# tiny-psu-exp-v1_1.net
KiCad netlist of a schematic drawn in EAGLE
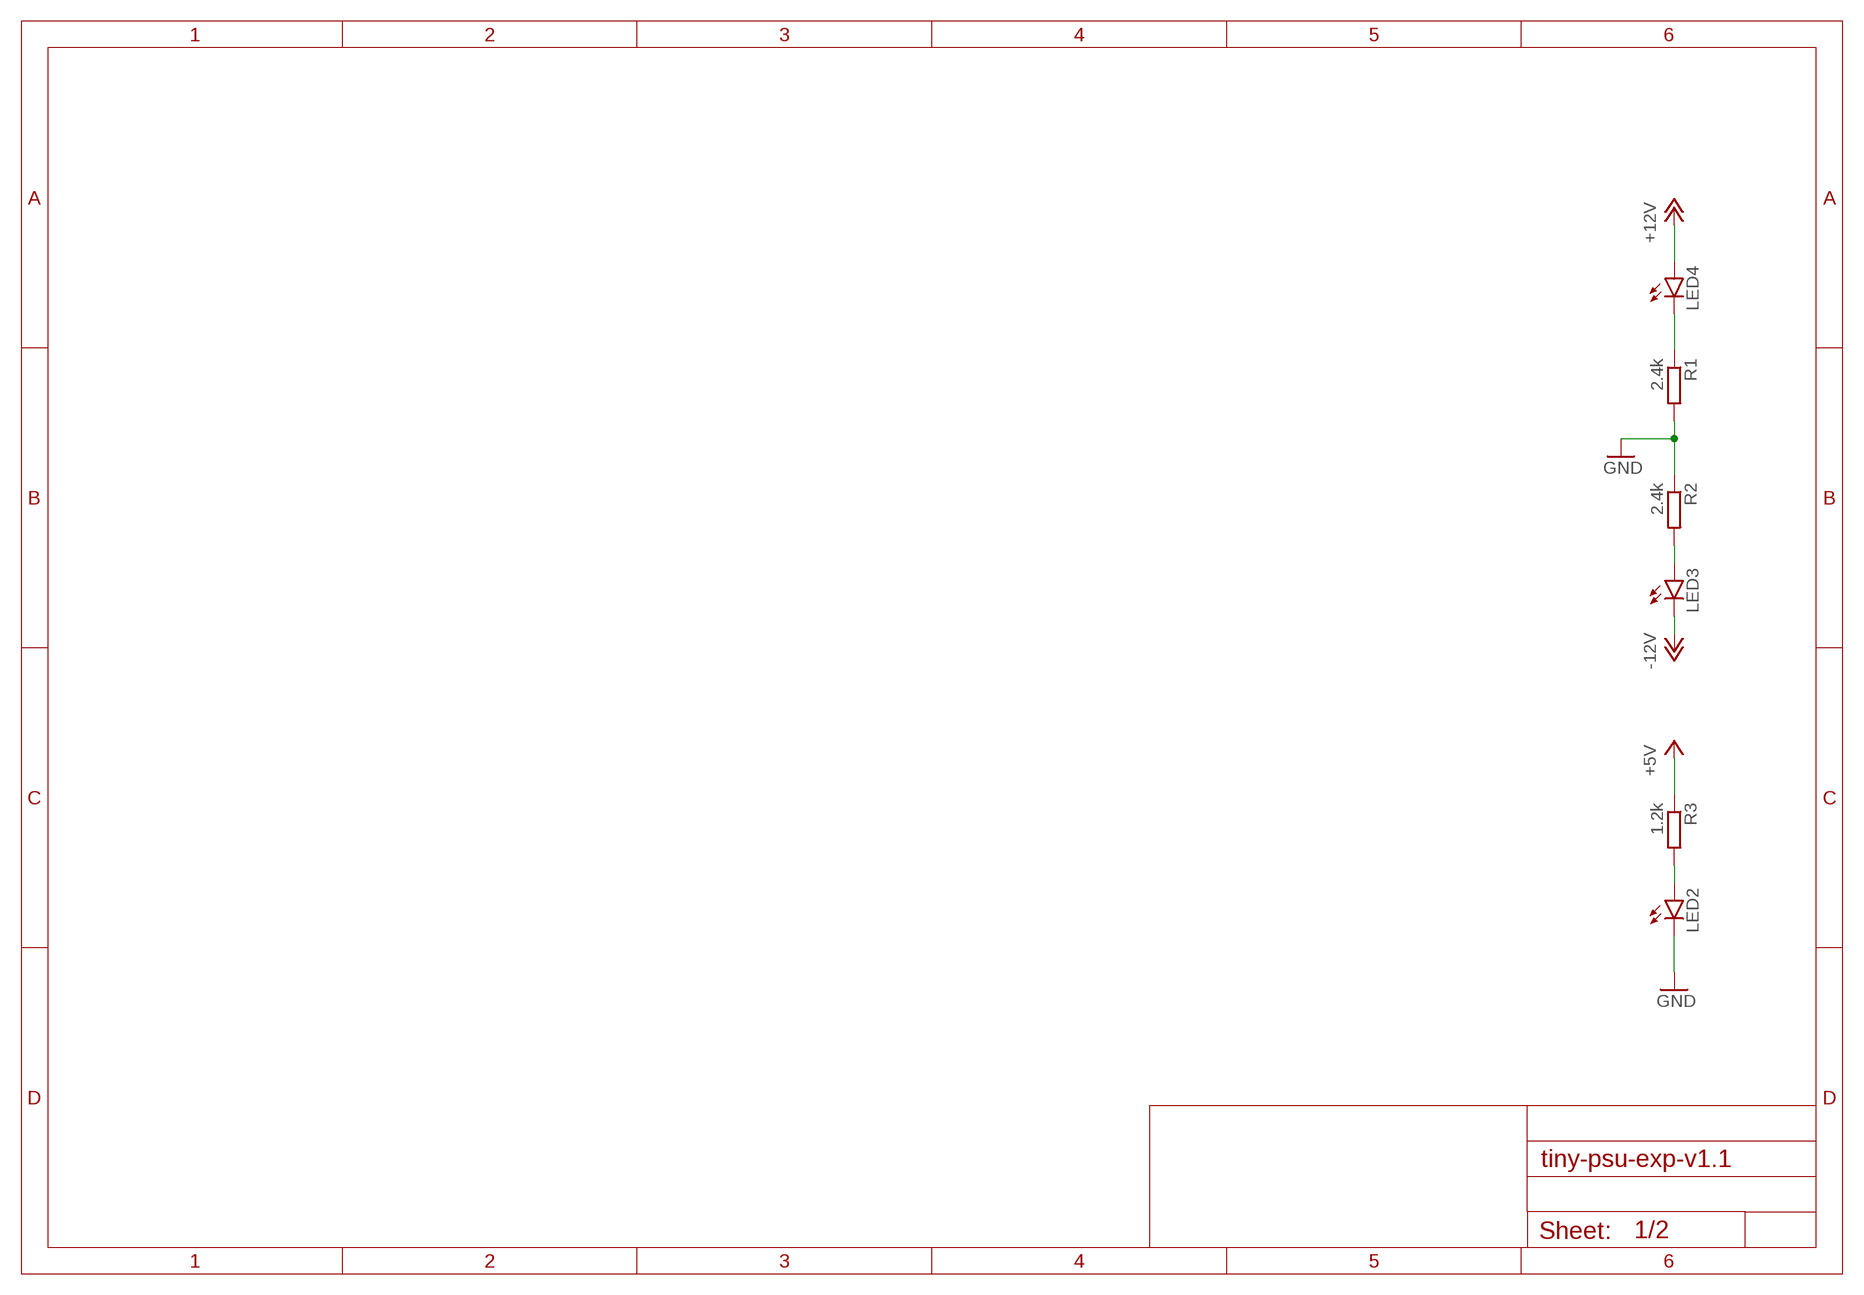
[diagram p0: schematic, sheet 1]
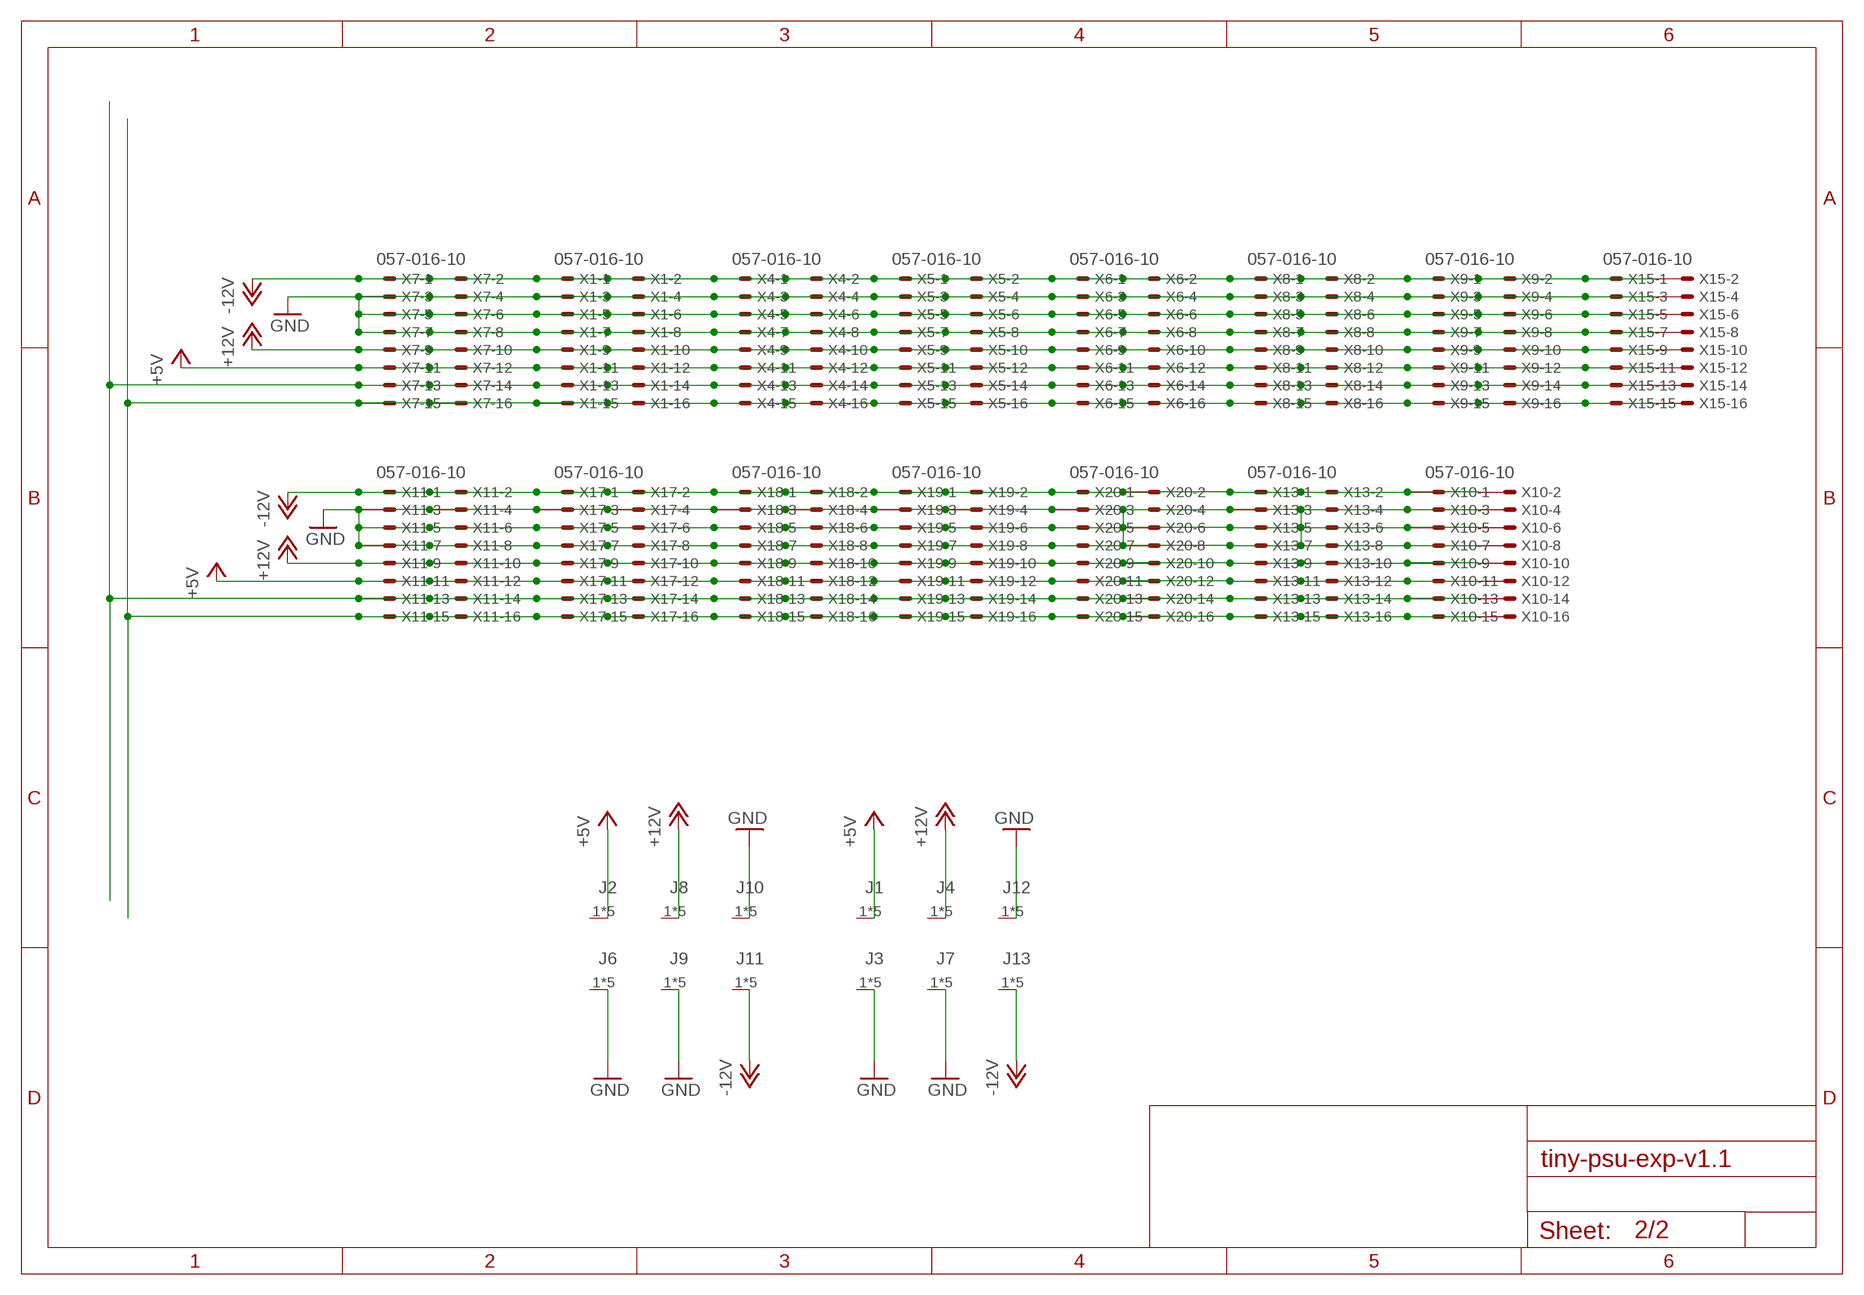
[diagram p1: schematic, sheet 2]

(export (version "E")
  (design (tool "Eeschema 10.0.6"))
  (components
    (comp (ref "J1")
      (value "30A-SCREW-CONN")
      (footprint "eagle-import:50X72")
      (libsource (lib "eagle-import") (part "30A-SCREW-CONN"))
    )
    (comp (ref "J2")
      (value "30A-SCREW-CONN")
      (footprint "eagle-import:50X72")
      (libsource (lib "eagle-import") (part "30A-SCREW-CONN"))
    )
    (comp (ref "J3")
      (value "30A-SCREW-CONN")
      (footprint "eagle-import:50X72")
      (libsource (lib "eagle-import") (part "30A-SCREW-CONN"))
    )
    (comp (ref "J4")
      (value "30A-SCREW-CONN")
      (footprint "eagle-import:50X72")
      (libsource (lib "eagle-import") (part "30A-SCREW-CONN"))
    )
    (comp (ref "J6")
      (value "30A-SCREW-CONN")
      (footprint "eagle-import:50X72")
      (libsource (lib "eagle-import") (part "30A-SCREW-CONN"))
    )
    (comp (ref "J7")
      (value "30A-SCREW-CONN")
      (footprint "eagle-import:50X72")
      (libsource (lib "eagle-import") (part "30A-SCREW-CONN"))
    )
    (comp (ref "J8")
      (value "30A-SCREW-CONN")
      (footprint "eagle-import:50X72")
      (libsource (lib "eagle-import") (part "30A-SCREW-CONN"))
    )
    (comp (ref "J9")
      (value "30A-SCREW-CONN")
      (footprint "eagle-import:50X72")
      (libsource (lib "eagle-import") (part "30A-SCREW-CONN"))
    )
    (comp (ref "J10")
      (value "30A-SCREW-CONN")
      (footprint "eagle-import:50X72")
      (libsource (lib "eagle-import") (part "30A-SCREW-CONN"))
    )
    (comp (ref "J11")
      (value "30A-SCREW-CONN")
      (footprint "eagle-import:50X72")
      (libsource (lib "eagle-import") (part "30A-SCREW-CONN"))
    )
    (comp (ref "J12")
      (value "30A-SCREW-CONN")
      (footprint "eagle-import:50X72")
      (libsource (lib "eagle-import") (part "30A-SCREW-CONN"))
    )
    (comp (ref "J13")
      (value "30A-SCREW-CONN")
      (footprint "eagle-import:50X72")
      (libsource (lib "eagle-import") (part "30A-SCREW-CONN"))
    )
    (comp (ref "X1")
      (value "057-016-10")
      (footprint "eagle-import:057-016-1")
      (libsource (lib "eagle-import") (part "057-016-10"))
    )
    (comp (ref "X4")
      (value "057-016-10")
      (footprint "eagle-import:057-016-1")
      (libsource (lib "eagle-import") (part "057-016-10"))
    )
    (comp (ref "X5")
      (value "057-016-10")
      (footprint "eagle-import:057-016-1")
      (libsource (lib "eagle-import") (part "057-016-10"))
    )
    (comp (ref "X6")
      (value "057-016-10")
      (footprint "eagle-import:057-016-1")
      (libsource (lib "eagle-import") (part "057-016-10"))
    )
    (comp (ref "X7")
      (value "057-016-10")
      (footprint "eagle-import:057-016-1")
      (libsource (lib "eagle-import") (part "057-016-10"))
    )
    (comp (ref "X8")
      (value "057-016-10")
      (footprint "eagle-import:057-016-1")
      (libsource (lib "eagle-import") (part "057-016-10"))
    )
    (comp (ref "X9")
      (value "057-016-10")
      (footprint "eagle-import:057-016-1")
      (libsource (lib "eagle-import") (part "057-016-10"))
    )
    (comp (ref "X10")
      (value "057-016-10")
      (footprint "eagle-import:057-016-1")
      (libsource (lib "eagle-import") (part "057-016-10"))
    )
    (comp (ref "X11")
      (value "057-016-10")
      (footprint "eagle-import:057-016-1")
      (libsource (lib "eagle-import") (part "057-016-10"))
    )
    (comp (ref "X13")
      (value "057-016-10")
      (footprint "eagle-import:057-016-1")
      (libsource (lib "eagle-import") (part "057-016-10"))
    )
    (comp (ref "X15")
      (value "057-016-10")
      (footprint "eagle-import:057-016-1")
      (libsource (lib "eagle-import") (part "057-016-10"))
    )
    (comp (ref "X17")
      (value "057-016-10")
      (footprint "eagle-import:057-016-1")
      (libsource (lib "eagle-import") (part "057-016-10"))
    )
    (comp (ref "X18")
      (value "057-016-10")
      (footprint "eagle-import:057-016-1")
      (libsource (lib "eagle-import") (part "057-016-10"))
    )
    (comp (ref "X19")
      (value "057-016-10")
      (footprint "eagle-import:057-016-1")
      (libsource (lib "eagle-import") (part "057-016-10"))
    )
    (comp (ref "X20")
      (value "057-016-10")
      (footprint "eagle-import:057-016-1")
      (libsource (lib "eagle-import") (part "057-016-10"))
    )
    (comp (ref "LED2")
      (value "LEDCHIP-LED0805")
      (footprint "eagle-import:CHIP-LED0805")
      (libsource (lib "eagle-import") (part "LEDCHIP-LED0805"))
    )
    (comp (ref "LED3")
      (value "LEDCHIP-LED0805")
      (footprint "eagle-import:CHIP-LED0805")
      (libsource (lib "eagle-import") (part "LEDCHIP-LED0805"))
    )
    (comp (ref "LED4")
      (value "LEDCHIP-LED0805")
      (footprint "eagle-import:CHIP-LED0805")
      (libsource (lib "eagle-import") (part "LEDCHIP-LED0805"))
    )
    (comp (ref "R1")
      (value "2.4k")
      (footprint "eagle-import:R0805")
      (libsource (lib "eagle-import") (part "R-EU_R0805"))
    )
    (comp (ref "R2")
      (value "2.4k")
      (footprint "eagle-import:R0805")
      (libsource (lib "eagle-import") (part "R-EU_R0805"))
    )
    (comp (ref "R3")
      (value "1.2k")
      (footprint "eagle-import:R0805")
      (libsource (lib "eagle-import") (part "R-EU_R0805"))
    )
  )
  (nets
    (net (code "1") (name "+5V") (class "Default")
      (node (ref "J1") (pin "1") (pinfunction "2_1") (pintype "passive"))
      (node (ref "J1") (pin "2") (pinfunction "2_2") (pintype "passive"))
      (node (ref "J1") (pin "3") (pinfunction "2_3") (pintype "passive"))
      (node (ref "J1") (pin "4") (pinfunction "2_4") (pintype "passive"))
      (node (ref "J1") (pin "P$1") (pinfunction "2_P$1") (pintype "passive"))
      (node (ref "J2") (pin "1") (pinfunction "2_1") (pintype "passive"))
      (node (ref "J2") (pin "2") (pinfunction "2_2") (pintype "passive"))
      (node (ref "J2") (pin "3") (pinfunction "2_3") (pintype "passive"))
      (node (ref "J2") (pin "4") (pinfunction "2_4") (pintype "passive"))
      (node (ref "J2") (pin "P$1") (pinfunction "2_P$1") (pintype "passive"))
      (node (ref "R3") (pin "1") (pinfunction "1_1") (pintype "passive"))
      (node (ref "X1") (pin "11") (pinfunction "S_11") (pintype "passive"))
      (node (ref "X1") (pin "12") (pinfunction "S_12") (pintype "passive"))
      (node (ref "X10") (pin "11") (pinfunction "S_11") (pintype "passive"))
      (node (ref "X10") (pin "12") (pinfunction "S_12") (pintype "passive"))
      (node (ref "X11") (pin "11") (pinfunction "S_11") (pintype "passive"))
      (node (ref "X11") (pin "12") (pinfunction "S_12") (pintype "passive"))
      (node (ref "X13") (pin "11") (pinfunction "S_11") (pintype "passive"))
      (node (ref "X13") (pin "12") (pinfunction "S_12") (pintype "passive"))
      (node (ref "X15") (pin "11") (pinfunction "S_11") (pintype "passive"))
      (node (ref "X15") (pin "12") (pinfunction "S_12") (pintype "passive"))
      (node (ref "X17") (pin "11") (pinfunction "S_11") (pintype "passive"))
      (node (ref "X17") (pin "12") (pinfunction "S_12") (pintype "passive"))
      (node (ref "X18") (pin "11") (pinfunction "S_11") (pintype "passive"))
      (node (ref "X18") (pin "12") (pinfunction "S_12") (pintype "passive"))
      (node (ref "X19") (pin "11") (pinfunction "S_11") (pintype "passive"))
      (node (ref "X19") (pin "12") (pinfunction "S_12") (pintype "passive"))
      (node (ref "X20") (pin "11") (pinfunction "S_11") (pintype "passive"))
      (node (ref "X20") (pin "12") (pinfunction "S_12") (pintype "passive"))
      (node (ref "X4") (pin "11") (pinfunction "S_11") (pintype "passive"))
      (node (ref "X4") (pin "12") (pinfunction "S_12") (pintype "passive"))
      (node (ref "X5") (pin "11") (pinfunction "S_11") (pintype "passive"))
      (node (ref "X5") (pin "12") (pinfunction "S_12") (pintype "passive"))
      (node (ref "X6") (pin "11") (pinfunction "S_11") (pintype "passive"))
      (node (ref "X6") (pin "12") (pinfunction "S_12") (pintype "passive"))
      (node (ref "X7") (pin "11") (pinfunction "S_11") (pintype "passive"))
      (node (ref "X7") (pin "12") (pinfunction "S_12") (pintype "passive"))
      (node (ref "X8") (pin "11") (pinfunction "S_11") (pintype "passive"))
      (node (ref "X8") (pin "12") (pinfunction "S_12") (pintype "passive"))
      (node (ref "X9") (pin "11") (pinfunction "S_11") (pintype "passive"))
      (node (ref "X9") (pin "12") (pinfunction "S_12") (pintype "passive"))
    )
    (net (code "2") (name "+12V") (class "Default")
      (node (ref "J4") (pin "1") (pinfunction "2_1") (pintype "passive"))
      (node (ref "J4") (pin "2") (pinfunction "2_2") (pintype "passive"))
      (node (ref "J4") (pin "3") (pinfunction "2_3") (pintype "passive"))
      (node (ref "J4") (pin "4") (pinfunction "2_4") (pintype "passive"))
      (node (ref "J4") (pin "P$1") (pinfunction "2_P$1") (pintype "passive"))
      (node (ref "J8") (pin "1") (pinfunction "2_1") (pintype "passive"))
      (node (ref "J8") (pin "2") (pinfunction "2_2") (pintype "passive"))
      (node (ref "J8") (pin "3") (pinfunction "2_3") (pintype "passive"))
      (node (ref "J8") (pin "4") (pinfunction "2_4") (pintype "passive"))
      (node (ref "J8") (pin "P$1") (pinfunction "2_P$1") (pintype "passive"))
      (node (ref "LED4") (pin "A") (pinfunction "A_A") (pintype "passive"))
      (node (ref "X1") (pin "10") (pinfunction "S_10") (pintype "passive"))
      (node (ref "X1") (pin "9") (pinfunction "S_9") (pintype "passive"))
      (node (ref "X10") (pin "10") (pinfunction "S_10") (pintype "passive"))
      (node (ref "X10") (pin "9") (pinfunction "S_9") (pintype "passive"))
      (node (ref "X11") (pin "10") (pinfunction "S_10") (pintype "passive"))
      (node (ref "X11") (pin "9") (pinfunction "S_9") (pintype "passive"))
      (node (ref "X13") (pin "10") (pinfunction "S_10") (pintype "passive"))
      (node (ref "X13") (pin "9") (pinfunction "S_9") (pintype "passive"))
      (node (ref "X15") (pin "10") (pinfunction "S_10") (pintype "passive"))
      (node (ref "X15") (pin "9") (pinfunction "S_9") (pintype "passive"))
      (node (ref "X17") (pin "10") (pinfunction "S_10") (pintype "passive"))
      (node (ref "X17") (pin "9") (pinfunction "S_9") (pintype "passive"))
      (node (ref "X18") (pin "10") (pinfunction "S_10") (pintype "passive"))
      (node (ref "X18") (pin "9") (pinfunction "S_9") (pintype "passive"))
      (node (ref "X19") (pin "10") (pinfunction "S_10") (pintype "passive"))
      (node (ref "X19") (pin "9") (pinfunction "S_9") (pintype "passive"))
      (node (ref "X20") (pin "10") (pinfunction "S_10") (pintype "passive"))
      (node (ref "X20") (pin "9") (pinfunction "S_9") (pintype "passive"))
      (node (ref "X4") (pin "10") (pinfunction "S_10") (pintype "passive"))
      (node (ref "X4") (pin "9") (pinfunction "S_9") (pintype "passive"))
      (node (ref "X5") (pin "10") (pinfunction "S_10") (pintype "passive"))
      (node (ref "X5") (pin "9") (pinfunction "S_9") (pintype "passive"))
      (node (ref "X6") (pin "10") (pinfunction "S_10") (pintype "passive"))
      (node (ref "X6") (pin "9") (pinfunction "S_9") (pintype "passive"))
      (node (ref "X7") (pin "10") (pinfunction "S_10") (pintype "passive"))
      (node (ref "X7") (pin "9") (pinfunction "S_9") (pintype "passive"))
      (node (ref "X8") (pin "10") (pinfunction "S_10") (pintype "passive"))
      (node (ref "X8") (pin "9") (pinfunction "S_9") (pintype "passive"))
      (node (ref "X9") (pin "10") (pinfunction "S_10") (pintype "passive"))
      (node (ref "X9") (pin "9") (pinfunction "S_9") (pintype "passive"))
    )
    (net (code "3") (name "-12V") (class "Default")
      (node (ref "J11") (pin "1") (pinfunction "2_1") (pintype "passive"))
      (node (ref "J11") (pin "2") (pinfunction "2_2") (pintype "passive"))
      (node (ref "J11") (pin "3") (pinfunction "2_3") (pintype "passive"))
      (node (ref "J11") (pin "4") (pinfunction "2_4") (pintype "passive"))
      (node (ref "J11") (pin "P$1") (pinfunction "2_P$1") (pintype "passive"))
      (node (ref "J13") (pin "1") (pinfunction "2_1") (pintype "passive"))
      (node (ref "J13") (pin "2") (pinfunction "2_2") (pintype "passive"))
      (node (ref "J13") (pin "3") (pinfunction "2_3") (pintype "passive"))
      (node (ref "J13") (pin "4") (pinfunction "2_4") (pintype "passive"))
      (node (ref "J13") (pin "P$1") (pinfunction "2_P$1") (pintype "passive"))
      (node (ref "LED3") (pin "C") (pinfunction "C_C") (pintype "passive"))
      (node (ref "X1") (pin "1") (pinfunction "S_1") (pintype "passive"))
      (node (ref "X1") (pin "2") (pinfunction "S_2") (pintype "passive"))
      (node (ref "X10") (pin "1") (pinfunction "S_1") (pintype "passive"))
      (node (ref "X10") (pin "2") (pinfunction "S_2") (pintype "passive"))
      (node (ref "X11") (pin "1") (pinfunction "S_1") (pintype "passive"))
      (node (ref "X11") (pin "2") (pinfunction "S_2") (pintype "passive"))
      (node (ref "X13") (pin "1") (pinfunction "S_1") (pintype "passive"))
      (node (ref "X13") (pin "2") (pinfunction "S_2") (pintype "passive"))
      (node (ref "X15") (pin "1") (pinfunction "S_1") (pintype "passive"))
      (node (ref "X15") (pin "2") (pinfunction "S_2") (pintype "passive"))
      (node (ref "X17") (pin "1") (pinfunction "S_1") (pintype "passive"))
      (node (ref "X17") (pin "2") (pinfunction "S_2") (pintype "passive"))
      (node (ref "X18") (pin "1") (pinfunction "S_1") (pintype "passive"))
      (node (ref "X18") (pin "2") (pinfunction "S_2") (pintype "passive"))
      (node (ref "X19") (pin "1") (pinfunction "S_1") (pintype "passive"))
      (node (ref "X19") (pin "2") (pinfunction "S_2") (pintype "passive"))
      (node (ref "X20") (pin "1") (pinfunction "S_1") (pintype "passive"))
      (node (ref "X20") (pin "2") (pinfunction "S_2") (pintype "passive"))
      (node (ref "X4") (pin "1") (pinfunction "S_1") (pintype "passive"))
      (node (ref "X4") (pin "2") (pinfunction "S_2") (pintype "passive"))
      (node (ref "X5") (pin "1") (pinfunction "S_1") (pintype "passive"))
      (node (ref "X5") (pin "2") (pinfunction "S_2") (pintype "passive"))
      (node (ref "X6") (pin "1") (pinfunction "S_1") (pintype "passive"))
      (node (ref "X6") (pin "2") (pinfunction "S_2") (pintype "passive"))
      (node (ref "X7") (pin "1") (pinfunction "S_1") (pintype "passive"))
      (node (ref "X7") (pin "2") (pinfunction "S_2") (pintype "passive"))
      (node (ref "X8") (pin "1") (pinfunction "S_1") (pintype "passive"))
      (node (ref "X8") (pin "2") (pinfunction "S_2") (pintype "passive"))
      (node (ref "X9") (pin "1") (pinfunction "S_1") (pintype "passive"))
      (node (ref "X9") (pin "2") (pinfunction "S_2") (pintype "passive"))
    )
    (net (code "4") (name "GND") (class "Default")
      (node (ref "J10") (pin "1") (pinfunction "2_1") (pintype "passive"))
      (node (ref "J10") (pin "2") (pinfunction "2_2") (pintype "passive"))
      (node (ref "J10") (pin "3") (pinfunction "2_3") (pintype "passive"))
      (node (ref "J10") (pin "4") (pinfunction "2_4") (pintype "passive"))
      (node (ref "J10") (pin "P$1") (pinfunction "2_P$1") (pintype "passive"))
      (node (ref "J12") (pin "1") (pinfunction "2_1") (pintype "passive"))
      (node (ref "J12") (pin "2") (pinfunction "2_2") (pintype "passive"))
      (node (ref "J12") (pin "3") (pinfunction "2_3") (pintype "passive"))
      (node (ref "J12") (pin "4") (pinfunction "2_4") (pintype "passive"))
      (node (ref "J12") (pin "P$1") (pinfunction "2_P$1") (pintype "passive"))
      (node (ref "J3") (pin "1") (pinfunction "2_1") (pintype "passive"))
      (node (ref "J3") (pin "2") (pinfunction "2_2") (pintype "passive"))
      (node (ref "J3") (pin "3") (pinfunction "2_3") (pintype "passive"))
      (node (ref "J3") (pin "4") (pinfunction "2_4") (pintype "passive"))
      (node (ref "J3") (pin "P$1") (pinfunction "2_P$1") (pintype "passive"))
      (node (ref "J6") (pin "1") (pinfunction "2_1") (pintype "passive"))
      (node (ref "J6") (pin "2") (pinfunction "2_2") (pintype "passive"))
      (node (ref "J6") (pin "3") (pinfunction "2_3") (pintype "passive"))
      (node (ref "J6") (pin "4") (pinfunction "2_4") (pintype "passive"))
      (node (ref "J6") (pin "P$1") (pinfunction "2_P$1") (pintype "passive"))
      (node (ref "J7") (pin "1") (pinfunction "2_1") (pintype "passive"))
      (node (ref "J7") (pin "2") (pinfunction "2_2") (pintype "passive"))
      (node (ref "J7") (pin "3") (pinfunction "2_3") (pintype "passive"))
      (node (ref "J7") (pin "4") (pinfunction "2_4") (pintype "passive"))
      (node (ref "J7") (pin "P$1") (pinfunction "2_P$1") (pintype "passive"))
      (node (ref "J9") (pin "1") (pinfunction "2_1") (pintype "passive"))
      (node (ref "J9") (pin "2") (pinfunction "2_2") (pintype "passive"))
      (node (ref "J9") (pin "3") (pinfunction "2_3") (pintype "passive"))
      (node (ref "J9") (pin "4") (pinfunction "2_4") (pintype "passive"))
      (node (ref "J9") (pin "P$1") (pinfunction "2_P$1") (pintype "passive"))
      (node (ref "LED2") (pin "C") (pinfunction "C_C") (pintype "passive"))
      (node (ref "R1") (pin "2") (pinfunction "2_2") (pintype "passive"))
      (node (ref "R2") (pin "1") (pinfunction "1_1") (pintype "passive"))
      (node (ref "X1") (pin "3") (pinfunction "S_3") (pintype "passive"))
      (node (ref "X1") (pin "4") (pinfunction "S_4") (pintype "passive"))
      (node (ref "X1") (pin "5") (pinfunction "S_5") (pintype "passive"))
      (node (ref "X1") (pin "6") (pinfunction "S_6") (pintype "passive"))
      (node (ref "X1") (pin "7") (pinfunction "S_7") (pintype "passive"))
      (node (ref "X1") (pin "8") (pinfunction "S_8") (pintype "passive"))
      (node (ref "X10") (pin "3") (pinfunction "S_3") (pintype "passive"))
      (node (ref "X10") (pin "4") (pinfunction "S_4") (pintype "passive"))
      (node (ref "X10") (pin "5") (pinfunction "S_5") (pintype "passive"))
      (node (ref "X10") (pin "6") (pinfunction "S_6") (pintype "passive"))
      (node (ref "X10") (pin "7") (pinfunction "S_7") (pintype "passive"))
      (node (ref "X10") (pin "8") (pinfunction "S_8") (pintype "passive"))
      (node (ref "X11") (pin "3") (pinfunction "S_3") (pintype "passive"))
      (node (ref "X11") (pin "4") (pinfunction "S_4") (pintype "passive"))
      (node (ref "X11") (pin "5") (pinfunction "S_5") (pintype "passive"))
      (node (ref "X11") (pin "6") (pinfunction "S_6") (pintype "passive"))
      (node (ref "X11") (pin "7") (pinfunction "S_7") (pintype "passive"))
      (node (ref "X11") (pin "8") (pinfunction "S_8") (pintype "passive"))
      (node (ref "X13") (pin "3") (pinfunction "S_3") (pintype "passive"))
      (node (ref "X13") (pin "4") (pinfunction "S_4") (pintype "passive"))
      (node (ref "X13") (pin "5") (pinfunction "S_5") (pintype "passive"))
      (node (ref "X13") (pin "6") (pinfunction "S_6") (pintype "passive"))
      (node (ref "X13") (pin "7") (pinfunction "S_7") (pintype "passive"))
      (node (ref "X13") (pin "8") (pinfunction "S_8") (pintype "passive"))
      (node (ref "X15") (pin "3") (pinfunction "S_3") (pintype "passive"))
      (node (ref "X15") (pin "4") (pinfunction "S_4") (pintype "passive"))
      (node (ref "X15") (pin "5") (pinfunction "S_5") (pintype "passive"))
      (node (ref "X15") (pin "6") (pinfunction "S_6") (pintype "passive"))
      (node (ref "X15") (pin "7") (pinfunction "S_7") (pintype "passive"))
      (node (ref "X15") (pin "8") (pinfunction "S_8") (pintype "passive"))
      (node (ref "X17") (pin "3") (pinfunction "S_3") (pintype "passive"))
      (node (ref "X17") (pin "4") (pinfunction "S_4") (pintype "passive"))
      (node (ref "X17") (pin "5") (pinfunction "S_5") (pintype "passive"))
      (node (ref "X17") (pin "6") (pinfunction "S_6") (pintype "passive"))
      (node (ref "X17") (pin "7") (pinfunction "S_7") (pintype "passive"))
      (node (ref "X17") (pin "8") (pinfunction "S_8") (pintype "passive"))
      (node (ref "X18") (pin "3") (pinfunction "S_3") (pintype "passive"))
      (node (ref "X18") (pin "4") (pinfunction "S_4") (pintype "passive"))
      (node (ref "X18") (pin "5") (pinfunction "S_5") (pintype "passive"))
      (node (ref "X18") (pin "6") (pinfunction "S_6") (pintype "passive"))
      (node (ref "X18") (pin "7") (pinfunction "S_7") (pintype "passive"))
      (node (ref "X18") (pin "8") (pinfunction "S_8") (pintype "passive"))
      (node (ref "X19") (pin "3") (pinfunction "S_3") (pintype "passive"))
      (node (ref "X19") (pin "4") (pinfunction "S_4") (pintype "passive"))
      (node (ref "X19") (pin "5") (pinfunction "S_5") (pintype "passive"))
      (node (ref "X19") (pin "6") (pinfunction "S_6") (pintype "passive"))
      (node (ref "X19") (pin "7") (pinfunction "S_7") (pintype "passive"))
      (node (ref "X19") (pin "8") (pinfunction "S_8") (pintype "passive"))
      (node (ref "X20") (pin "3") (pinfunction "S_3") (pintype "passive"))
      (node (ref "X20") (pin "4") (pinfunction "S_4") (pintype "passive"))
      (node (ref "X20") (pin "5") (pinfunction "S_5") (pintype "passive"))
      (node (ref "X20") (pin "6") (pinfunction "S_6") (pintype "passive"))
      (node (ref "X20") (pin "7") (pinfunction "S_7") (pintype "passive"))
      (node (ref "X20") (pin "8") (pinfunction "S_8") (pintype "passive"))
      (node (ref "X4") (pin "3") (pinfunction "S_3") (pintype "passive"))
      (node (ref "X4") (pin "4") (pinfunction "S_4") (pintype "passive"))
      (node (ref "X4") (pin "5") (pinfunction "S_5") (pintype "passive"))
      (node (ref "X4") (pin "6") (pinfunction "S_6") (pintype "passive"))
      (node (ref "X4") (pin "7") (pinfunction "S_7") (pintype "passive"))
      (node (ref "X4") (pin "8") (pinfunction "S_8") (pintype "passive"))
      (node (ref "X5") (pin "3") (pinfunction "S_3") (pintype "passive"))
      (node (ref "X5") (pin "4") (pinfunction "S_4") (pintype "passive"))
      (node (ref "X5") (pin "5") (pinfunction "S_5") (pintype "passive"))
      (node (ref "X5") (pin "6") (pinfunction "S_6") (pintype "passive"))
      (node (ref "X5") (pin "7") (pinfunction "S_7") (pintype "passive"))
      (node (ref "X5") (pin "8") (pinfunction "S_8") (pintype "passive"))
      (node (ref "X6") (pin "3") (pinfunction "S_3") (pintype "passive"))
      (node (ref "X6") (pin "4") (pinfunction "S_4") (pintype "passive"))
      (node (ref "X6") (pin "5") (pinfunction "S_5") (pintype "passive"))
      (node (ref "X6") (pin "6") (pinfunction "S_6") (pintype "passive"))
      (node (ref "X6") (pin "7") (pinfunction "S_7") (pintype "passive"))
      (node (ref "X6") (pin "8") (pinfunction "S_8") (pintype "passive"))
      (node (ref "X7") (pin "3") (pinfunction "S_3") (pintype "passive"))
      (node (ref "X7") (pin "4") (pinfunction "S_4") (pintype "passive"))
      (node (ref "X7") (pin "5") (pinfunction "S_5") (pintype "passive"))
      (node (ref "X7") (pin "6") (pinfunction "S_6") (pintype "passive"))
      (node (ref "X7") (pin "7") (pinfunction "S_7") (pintype "passive"))
      (node (ref "X7") (pin "8") (pinfunction "S_8") (pintype "passive"))
      (node (ref "X8") (pin "3") (pinfunction "S_3") (pintype "passive"))
      (node (ref "X8") (pin "4") (pinfunction "S_4") (pintype "passive"))
      (node (ref "X8") (pin "5") (pinfunction "S_5") (pintype "passive"))
      (node (ref "X8") (pin "6") (pinfunction "S_6") (pintype "passive"))
      (node (ref "X8") (pin "7") (pinfunction "S_7") (pintype "passive"))
      (node (ref "X8") (pin "8") (pinfunction "S_8") (pintype "passive"))
      (node (ref "X9") (pin "3") (pinfunction "S_3") (pintype "passive"))
      (node (ref "X9") (pin "4") (pinfunction "S_4") (pintype "passive"))
      (node (ref "X9") (pin "5") (pinfunction "S_5") (pintype "passive"))
      (node (ref "X9") (pin "6") (pinfunction "S_6") (pintype "passive"))
      (node (ref "X9") (pin "7") (pinfunction "S_7") (pintype "passive"))
      (node (ref "X9") (pin "8") (pinfunction "S_8") (pintype "passive"))
    )
    (net (code "5") (name "Net-(LED2-PadA)") (class "Default")
      (node (ref "LED2") (pin "A") (pinfunction "A_A") (pintype "passive"))
      (node (ref "R3") (pin "2") (pinfunction "2_2") (pintype "passive"))
    )
    (net (code "6") (name "Net-(LED3-PadA)") (class "Default")
      (node (ref "LED3") (pin "A") (pinfunction "A_A") (pintype "passive"))
      (node (ref "R2") (pin "2") (pinfunction "2_2") (pintype "passive"))
    )
    (net (code "7") (name "Net-(LED4-PadC)") (class "Default")
      (node (ref "LED4") (pin "C") (pinfunction "C_C") (pintype "passive"))
      (node (ref "R1") (pin "1") (pinfunction "1_1") (pintype "passive"))
    )
    (net (code "8") (name "Net-(X10E-S)") (class "Default")
      (node (ref "X1") (pin "13") (pinfunction "S_13") (pintype "passive"))
      (node (ref "X1") (pin "14") (pinfunction "S_14") (pintype "passive"))
      (node (ref "X10") (pin "13") (pinfunction "S_13") (pintype "passive"))
      (node (ref "X10") (pin "14") (pinfunction "S_14") (pintype "passive"))
      (node (ref "X11") (pin "13") (pinfunction "S_13") (pintype "passive"))
      (node (ref "X11") (pin "14") (pinfunction "S_14") (pintype "passive"))
      (node (ref "X13") (pin "13") (pinfunction "S_13") (pintype "passive"))
      (node (ref "X13") (pin "14") (pinfunction "S_14") (pintype "passive"))
      (node (ref "X15") (pin "13") (pinfunction "S_13") (pintype "passive"))
      (node (ref "X15") (pin "14") (pinfunction "S_14") (pintype "passive"))
      (node (ref "X17") (pin "13") (pinfunction "S_13") (pintype "passive"))
      (node (ref "X17") (pin "14") (pinfunction "S_14") (pintype "passive"))
      (node (ref "X18") (pin "13") (pinfunction "S_13") (pintype "passive"))
      (node (ref "X18") (pin "14") (pinfunction "S_14") (pintype "passive"))
      (node (ref "X19") (pin "13") (pinfunction "S_13") (pintype "passive"))
      (node (ref "X19") (pin "14") (pinfunction "S_14") (pintype "passive"))
      (node (ref "X20") (pin "13") (pinfunction "S_13") (pintype "passive"))
      (node (ref "X20") (pin "14") (pinfunction "S_14") (pintype "passive"))
      (node (ref "X4") (pin "13") (pinfunction "S_13") (pintype "passive"))
      (node (ref "X4") (pin "14") (pinfunction "S_14") (pintype "passive"))
      (node (ref "X5") (pin "13") (pinfunction "S_13") (pintype "passive"))
      (node (ref "X5") (pin "14") (pinfunction "S_14") (pintype "passive"))
      (node (ref "X6") (pin "13") (pinfunction "S_13") (pintype "passive"))
      (node (ref "X6") (pin "14") (pinfunction "S_14") (pintype "passive"))
      (node (ref "X7") (pin "13") (pinfunction "S_13") (pintype "passive"))
      (node (ref "X7") (pin "14") (pinfunction "S_14") (pintype "passive"))
      (node (ref "X8") (pin "13") (pinfunction "S_13") (pintype "passive"))
      (node (ref "X8") (pin "14") (pinfunction "S_14") (pintype "passive"))
      (node (ref "X9") (pin "13") (pinfunction "S_13") (pintype "passive"))
      (node (ref "X9") (pin "14") (pinfunction "S_14") (pintype "passive"))
    )
    (net (code "9") (name "Net-(X10G-S)") (class "Default")
      (node (ref "X1") (pin "15") (pinfunction "S_15") (pintype "passive"))
      (node (ref "X1") (pin "16") (pinfunction "S_16") (pintype "passive"))
      (node (ref "X10") (pin "15") (pinfunction "S_15") (pintype "passive"))
      (node (ref "X10") (pin "16") (pinfunction "S_16") (pintype "passive"))
      (node (ref "X11") (pin "15") (pinfunction "S_15") (pintype "passive"))
      (node (ref "X11") (pin "16") (pinfunction "S_16") (pintype "passive"))
      (node (ref "X13") (pin "15") (pinfunction "S_15") (pintype "passive"))
      (node (ref "X13") (pin "16") (pinfunction "S_16") (pintype "passive"))
      (node (ref "X15") (pin "15") (pinfunction "S_15") (pintype "passive"))
      (node (ref "X15") (pin "16") (pinfunction "S_16") (pintype "passive"))
      (node (ref "X17") (pin "15") (pinfunction "S_15") (pintype "passive"))
      (node (ref "X17") (pin "16") (pinfunction "S_16") (pintype "passive"))
      (node (ref "X18") (pin "15") (pinfunction "S_15") (pintype "passive"))
      (node (ref "X18") (pin "16") (pinfunction "S_16") (pintype "passive"))
      (node (ref "X19") (pin "15") (pinfunction "S_15") (pintype "passive"))
      (node (ref "X19") (pin "16") (pinfunction "S_16") (pintype "passive"))
      (node (ref "X20") (pin "15") (pinfunction "S_15") (pintype "passive"))
      (node (ref "X20") (pin "16") (pinfunction "S_16") (pintype "passive"))
      (node (ref "X4") (pin "15") (pinfunction "S_15") (pintype "passive"))
      (node (ref "X4") (pin "16") (pinfunction "S_16") (pintype "passive"))
      (node (ref "X5") (pin "15") (pinfunction "S_15") (pintype "passive"))
      (node (ref "X5") (pin "16") (pinfunction "S_16") (pintype "passive"))
      (node (ref "X6") (pin "15") (pinfunction "S_15") (pintype "passive"))
      (node (ref "X6") (pin "16") (pinfunction "S_16") (pintype "passive"))
      (node (ref "X7") (pin "15") (pinfunction "S_15") (pintype "passive"))
      (node (ref "X7") (pin "16") (pinfunction "S_16") (pintype "passive"))
      (node (ref "X8") (pin "15") (pinfunction "S_15") (pintype "passive"))
      (node (ref "X8") (pin "16") (pinfunction "S_16") (pintype "passive"))
      (node (ref "X9") (pin "15") (pinfunction "S_15") (pintype "passive"))
      (node (ref "X9") (pin "16") (pinfunction "S_16") (pintype "passive"))
    )
  )
)
